# CanBusArduino.net
KiCad netlist of a schematic drawn in EAGLE
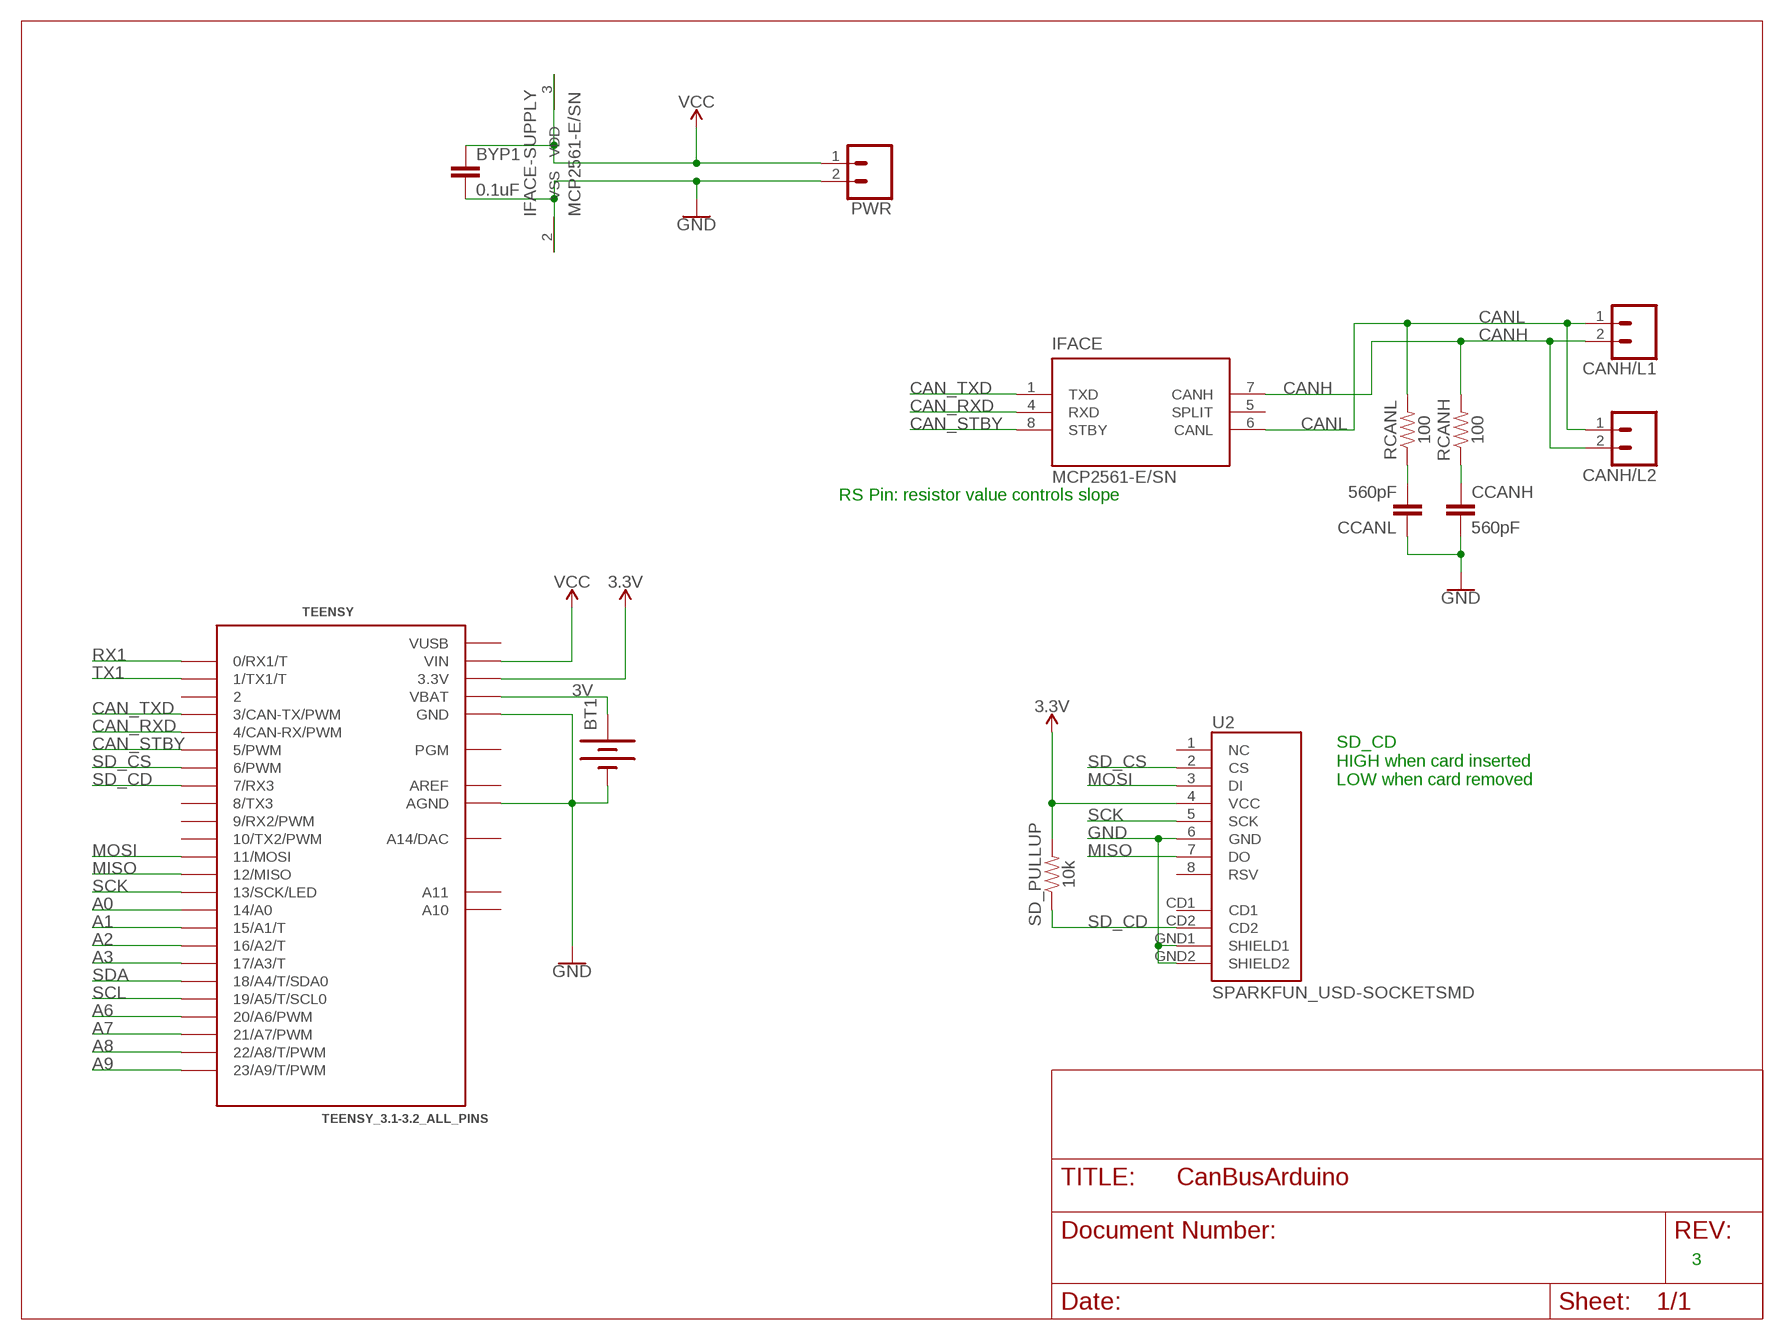
[diagram p0: schematic, sheet 1]

(export (version "E")
  (design (tool "Eeschema 10.0.6"))
  (components
    (comp (ref "BT1")
      (value "BATTERY-20MM_SMD_4LEGS")
      (footprint "eagle-import:BATTCON_20MM_4LEGS")
      (libsource (lib "eagle-import") (part "BATTERY-20MM_SMD_4LEGS"))
    )
    (comp (ref "BYP1")
      (value "0.1uF")
      (footprint "eagle-import:0603")
      (libsource (lib "eagle-import") (part "0.1UF-0603-100V-10%"))
    )
    (comp (ref "CANH/L1")
      (value "CONN_02POLAR")
      (footprint "eagle-import:MOLEX-1X2")
      (libsource (lib "eagle-import") (part "CONN_02POLAR"))
    )
    (comp (ref "CANH/L2")
      (value "CONN_02POLAR")
      (footprint "eagle-import:MOLEX-1X2")
      (libsource (lib "eagle-import") (part "CONN_02POLAR"))
    )
    (comp (ref "CCANH")
      (value "560pF")
      (footprint "eagle-import:0603")
      (libsource (lib "eagle-import") (part "560PF-0603-50V-5%"))
    )
    (comp (ref "CCANL")
      (value "560pF")
      (footprint "eagle-import:0603")
      (libsource (lib "eagle-import") (part "560PF-0603-50V-5%"))
    )
    (comp (ref "IFACE")
      (value "MCP2561-E/SN")
      (footprint "eagle-import:SOIC-8")
      (fields (field (name "MANUFACTURER") "Microchip Technology"))
      (libsource (lib "eagle-import") (part "MCP2561-/?SNE"))
    )
    (comp (ref "PWR")
      (value "CONN_02POLAR")
      (footprint "eagle-import:MOLEX-1X2")
      (libsource (lib "eagle-import") (part "CONN_02POLAR"))
    )
    (comp (ref "RCANH")
      (value "100")
      (footprint "eagle-import:0603")
      (libsource (lib "eagle-import") (part "100OHM-0603-1/4W-5%"))
    )
    (comp (ref "RCANL")
      (value "100")
      (footprint "eagle-import:0603")
      (libsource (lib "eagle-import") (part "100OHM-0603-1/4W-5%"))
    )
    (comp (ref "SD_PULLUP")
      (value "10k")
      (footprint "eagle-import:0603")
      (libsource (lib "eagle-import") (part "10KOHM-0603-1/10W-1%"))
    )
    (comp (ref "TEENSY")
      (value "TEENSY_3.1-3.2_ALL_PINS")
      (footprint "eagle-import:TEENSY_3.0-3.2&LC_ALL_PINS")
      (libsource (lib "eagle-import") (part "TEENSY_3.1-3.2_ALL_PINS"))
    )
    (comp (ref "U2")
      (value "SPARKFUN_USD-SOCKETSMD")
      (footprint "eagle-import:SPARKFUN_MICRO-SD-SOCKET-PP")
      (libsource (lib "eagle-import") (part "SPARKFUN_USD-SOCKETSMD"))
    )
  )
  (nets
    (net (code "1") (name "/3V") (class "Default")
      (node (ref "BT1") (pin "POSITIVE@1") (pinfunction "+_POSITIVE@1") (pintype "power_in"))
      (node (ref "BT1") (pin "POSITIVE@2") (pinfunction "+_POSITIVE@2") (pintype "power_in"))
      (node (ref "BT1") (pin "POSITIVE@3") (pinfunction "+_POSITIVE@3") (pintype "power_in"))
      (node (ref "BT1") (pin "POSITIVE@4") (pinfunction "+_POSITIVE@4") (pintype "power_in"))
      (node (ref "TEENSY") (pin "VBAT") (pinfunction "VBAT_VBAT") (pintype "power_in"))
    )
    (net (code "2") (name "/A0") (class "Default")
      (node (ref "TEENSY") (pin "14/A0") (pinfunction "14/A0_14/A0") (pintype "bidirectional"))
    )
    (net (code "3") (name "/A1") (class "Default")
      (node (ref "TEENSY") (pin "15/A1") (pinfunction "15/A1/T_15/A1") (pintype "bidirectional"))
    )
    (net (code "4") (name "/A2") (class "Default")
      (node (ref "TEENSY") (pin "16/A2") (pinfunction "16/A2/T_16/A2") (pintype "bidirectional"))
    )
    (net (code "5") (name "/A3") (class "Default")
      (node (ref "TEENSY") (pin "17/A3") (pinfunction "17/A3/T_17/A3") (pintype "bidirectional"))
    )
    (net (code "6") (name "/A6") (class "Default")
      (node (ref "TEENSY") (pin "20/A6") (pinfunction "20/A6/PWM_20/A6") (pintype "bidirectional"))
    )
    (net (code "7") (name "/A7") (class "Default")
      (node (ref "TEENSY") (pin "21/A7") (pinfunction "21/A7/PWM_21/A7") (pintype "bidirectional"))
    )
    (net (code "8") (name "/A8") (class "Default")
      (node (ref "TEENSY") (pin "22/A8") (pinfunction "22/A8/T/PWM_22/A8") (pintype "bidirectional"))
    )
    (net (code "9") (name "/A9") (class "Default")
      (node (ref "TEENSY") (pin "23/A9") (pinfunction "23/A9/T/PWM_23/A9") (pintype "bidirectional"))
    )
    (net (code "10") (name "/AREF") (class "Default")
      (node (ref "TEENSY") (pin "AREF") (pinfunction "AREF_AREF") (pintype "power_in"))
    )
    (net (code "11") (name "/CANH") (class "Default")
      (node (ref "CANH/L1") (pin "2") (pinfunction "2_2") (pintype "passive"))
      (node (ref "CANH/L2") (pin "2") (pinfunction "2_2") (pintype "passive"))
      (node (ref "IFACE") (pin "7") (pinfunction "CANH_7") (pintype "bidirectional"))
      (node (ref "RCANH") (pin "2") (pinfunction "2_2") (pintype "passive"))
    )
    (net (code "12") (name "/CANL") (class "Default")
      (node (ref "CANH/L1") (pin "1") (pinfunction "1_1") (pintype "passive"))
      (node (ref "CANH/L2") (pin "1") (pinfunction "1_1") (pintype "passive"))
      (node (ref "IFACE") (pin "6") (pinfunction "CANL_6") (pintype "bidirectional"))
      (node (ref "RCANL") (pin "2") (pinfunction "2_2") (pintype "passive"))
    )
    (net (code "13") (name "/CAN_RXD") (class "Default")
      (node (ref "IFACE") (pin "4") (pinfunction "RXD_4") (pintype "bidirectional"))
      (node (ref "TEENSY") (pin "4") (pinfunction "4/CAN-RX/PWM_4") (pintype "bidirectional"))
    )
    (net (code "14") (name "/CAN_STBY") (class "Default")
      (node (ref "IFACE") (pin "8") (pinfunction "STBY_8") (pintype "bidirectional"))
      (node (ref "TEENSY") (pin "5") (pinfunction "5/PWM_5") (pintype "bidirectional"))
    )
    (net (code "15") (name "/CAN_TXD") (class "Default")
      (node (ref "IFACE") (pin "1") (pinfunction "TXD_1") (pintype "bidirectional"))
      (node (ref "TEENSY") (pin "3") (pinfunction "3/CAN-TX/PWM_3") (pintype "bidirectional"))
    )
    (net (code "16") (name "/MISO") (class "Default")
      (node (ref "TEENSY") (pin "12") (pinfunction "12/MISO_12") (pintype "bidirectional"))
      (node (ref "U2") (pin "7") (pinfunction "DO_7") (pintype "bidirectional"))
    )
    (net (code "17") (name "/MOSI") (class "Default")
      (node (ref "TEENSY") (pin "11") (pinfunction "11/MOSI_11") (pintype "bidirectional"))
      (node (ref "U2") (pin "3") (pinfunction "DI_3") (pintype "bidirectional"))
    )
    (net (code "18") (name "/RX1") (class "Default")
      (node (ref "TEENSY") (pin "0") (pinfunction "0/RX1/T_0") (pintype "bidirectional"))
    )
    (net (code "19") (name "/SCK") (class "Default")
      (node (ref "TEENSY") (pin "13") (pinfunction "13/SCK/LED_13") (pintype "bidirectional"))
      (node (ref "U2") (pin "5") (pinfunction "SCK_5") (pintype "bidirectional"))
    )
    (net (code "20") (name "/SCL") (class "Default")
      (node (ref "TEENSY") (pin "19/A5") (pinfunction "19/A5/T/SCL0_19/A5") (pintype "bidirectional"))
    )
    (net (code "21") (name "/SDA") (class "Default")
      (node (ref "TEENSY") (pin "18/A4") (pinfunction "18/A4/T/SDA0_18/A4") (pintype "bidirectional"))
    )
    (net (code "22") (name "/SD_CD") (class "Default")
      (node (ref "SD_PULLUP") (pin "1") (pinfunction "1_1") (pintype "passive"))
      (node (ref "TEENSY") (pin "7") (pinfunction "7/RX3_7") (pintype "bidirectional"))
      (node (ref "U2") (pin "CD2") (pinfunction "CD2_CD2") (pintype "bidirectional"))
    )
    (net (code "23") (name "/SD_CS") (class "Default")
      (node (ref "TEENSY") (pin "6") (pinfunction "6/PWM_6") (pintype "bidirectional"))
      (node (ref "U2") (pin "2") (pinfunction "CS_2") (pintype "bidirectional"))
    )
    (net (code "24") (name "/TX1") (class "Default")
      (node (ref "TEENSY") (pin "1") (pinfunction "1/TX1/T_1") (pintype "bidirectional"))
    )
    (net (code "25") (name "/VUSB") (class "Default")
      (node (ref "TEENSY") (pin "VUSB") (pinfunction "VUSB_VUSB") (pintype "power_in"))
    )
    (net (code "26") (name "3.3V") (class "Default")
      (node (ref "SD_PULLUP") (pin "2") (pinfunction "2_2") (pintype "passive"))
      (node (ref "TEENSY") (pin "3.3V") (pinfunction "3.3V_3.3V") (pintype "power_in"))
      (node (ref "TEENSY") (pin "3.3V1") (pinfunction "3.3V_3.3V1") (pintype "power_in"))
      (node (ref "U2") (pin "4") (pinfunction "VCC_4") (pintype "bidirectional"))
    )
    (net (code "27") (name "GND") (class "Default")
      (node (ref "BT1") (pin "NEGATIVE") (pinfunction "-_NEGATIVE") (pintype "power_in"))
      (node (ref "BYP1") (pin "2") (pinfunction "2_2") (pintype "passive"))
      (node (ref "CCANH") (pin "2") (pinfunction "2_2") (pintype "passive"))
      (node (ref "CCANL") (pin "1") (pinfunction "1_1") (pintype "passive"))
      (node (ref "IFACE") (pin "2") (pinfunction "VSS_2") (pintype "power_in"))
      (node (ref "PWR") (pin "2") (pinfunction "2_2") (pintype "passive"))
      (node (ref "TEENSY") (pin "AGND") (pinfunction "AGND_AGND") (pintype "power_in"))
      (node (ref "TEENSY") (pin "GND") (pinfunction "GND_GND") (pintype "power_in"))
      (node (ref "TEENSY") (pin "GND1") (pinfunction "GND_GND1") (pintype "power_in"))
      (node (ref "U2") (pin "6") (pinfunction "GND_6") (pintype "bidirectional"))
      (node (ref "U2") (pin "GND1") (pinfunction "SHIELD1_GND1") (pintype "bidirectional"))
      (node (ref "U2") (pin "GND2") (pinfunction "SHIELD2_GND2") (pintype "bidirectional"))
    )
    (net (code "28") (name "Net-(CCANH-Pad1)") (class "Default")
      (node (ref "CCANH") (pin "1") (pinfunction "1_1") (pintype "passive"))
      (node (ref "RCANH") (pin "1") (pinfunction "1_1") (pintype "passive"))
    )
    (net (code "29") (name "Net-(CCANL-Pad2)") (class "Default")
      (node (ref "CCANL") (pin "2") (pinfunction "2_2") (pintype "passive"))
      (node (ref "RCANL") (pin "1") (pinfunction "1_1") (pintype "passive"))
    )
    (net (code "30") (name "VCC") (class "Default")
      (node (ref "BYP1") (pin "1") (pinfunction "1_1") (pintype "passive"))
      (node (ref "IFACE") (pin "3") (pinfunction "VDD_3") (pintype "power_in"))
      (node (ref "PWR") (pin "1") (pinfunction "1_1") (pintype "passive"))
      (node (ref "TEENSY") (pin "VIN") (pinfunction "VIN_VIN") (pintype "power_in"))
    )
    (net (code "31") (name "unconnected-(IFACEB-SPLIT-Pad5)") (class "Default")
      (node (ref "IFACE") (pin "5") (pinfunction "SPLIT_5") (pintype "bidirectional"))
    )
    (net (code "32") (name "unconnected-(TEENSY-8{slash}TX3-Pad8)") (class "Default")
      (node (ref "TEENSY") (pin "8") (pinfunction "8/TX3_8") (pintype "bidirectional"))
    )
    (net (code "33") (name "unconnected-(TEENSY-9{slash}RX2{slash}PWM-Pad9)") (class "Default")
      (node (ref "TEENSY") (pin "9") (pinfunction "9/RX2/PWM_9") (pintype "bidirectional"))
    )
    (net (code "34") (name "unconnected-(TEENSY-10{slash}TX2{slash}PWM-Pad10)") (class "Default")
      (node (ref "TEENSY") (pin "10") (pinfunction "10/TX2/PWM_10") (pintype "bidirectional"))
    )
    (net (code "35") (name "unconnected-(TEENSY-A14{slash}DAC-PadRESET{slash}DAC)") (class "Default")
      (node (ref "TEENSY") (pin "RESET/DAC") (pinfunction "A14/DAC_RESET/DAC") (pintype "bidirectional"))
    )
    (net (code "36") (name "unconnected-(TEENSY-Pad2)") (class "Default")
      (node (ref "TEENSY") (pin "2") (pinfunction "2_2") (pintype "bidirectional"))
    )
    (net (code "37") (name "unconnected-(TEENSY-PadA10)") (class "Default")
      (node (ref "TEENSY") (pin "A10") (pinfunction "A10_A10") (pintype "bidirectional"))
    )
    (net (code "38") (name "unconnected-(TEENSY-PadA11)") (class "Default")
      (node (ref "TEENSY") (pin "A11") (pinfunction "A11_A11") (pintype "bidirectional"))
    )
    (net (code "39") (name "unconnected-(TEENSY-PadPGM)") (class "Default")
      (node (ref "TEENSY") (pin "PGM") (pinfunction "PGM_PGM") (pintype "bidirectional"))
    )
    (net (code "40") (name "unconnected-(U2-NC-Pad1)") (class "Default")
      (node (ref "U2") (pin "1") (pinfunction "NC_1") (pintype "bidirectional"))
    )
    (net (code "41") (name "unconnected-(U2-PadCD1)") (class "Default")
      (node (ref "U2") (pin "CD1") (pinfunction "CD1_CD1") (pintype "bidirectional"))
    )
    (net (code "42") (name "unconnected-(U2-RSV-Pad8)") (class "Default")
      (node (ref "U2") (pin "8") (pinfunction "RSV_8") (pintype "bidirectional"))
    )
  )
)
